# LDR.net
KiCad netlist of a schematic drawn in EAGLE
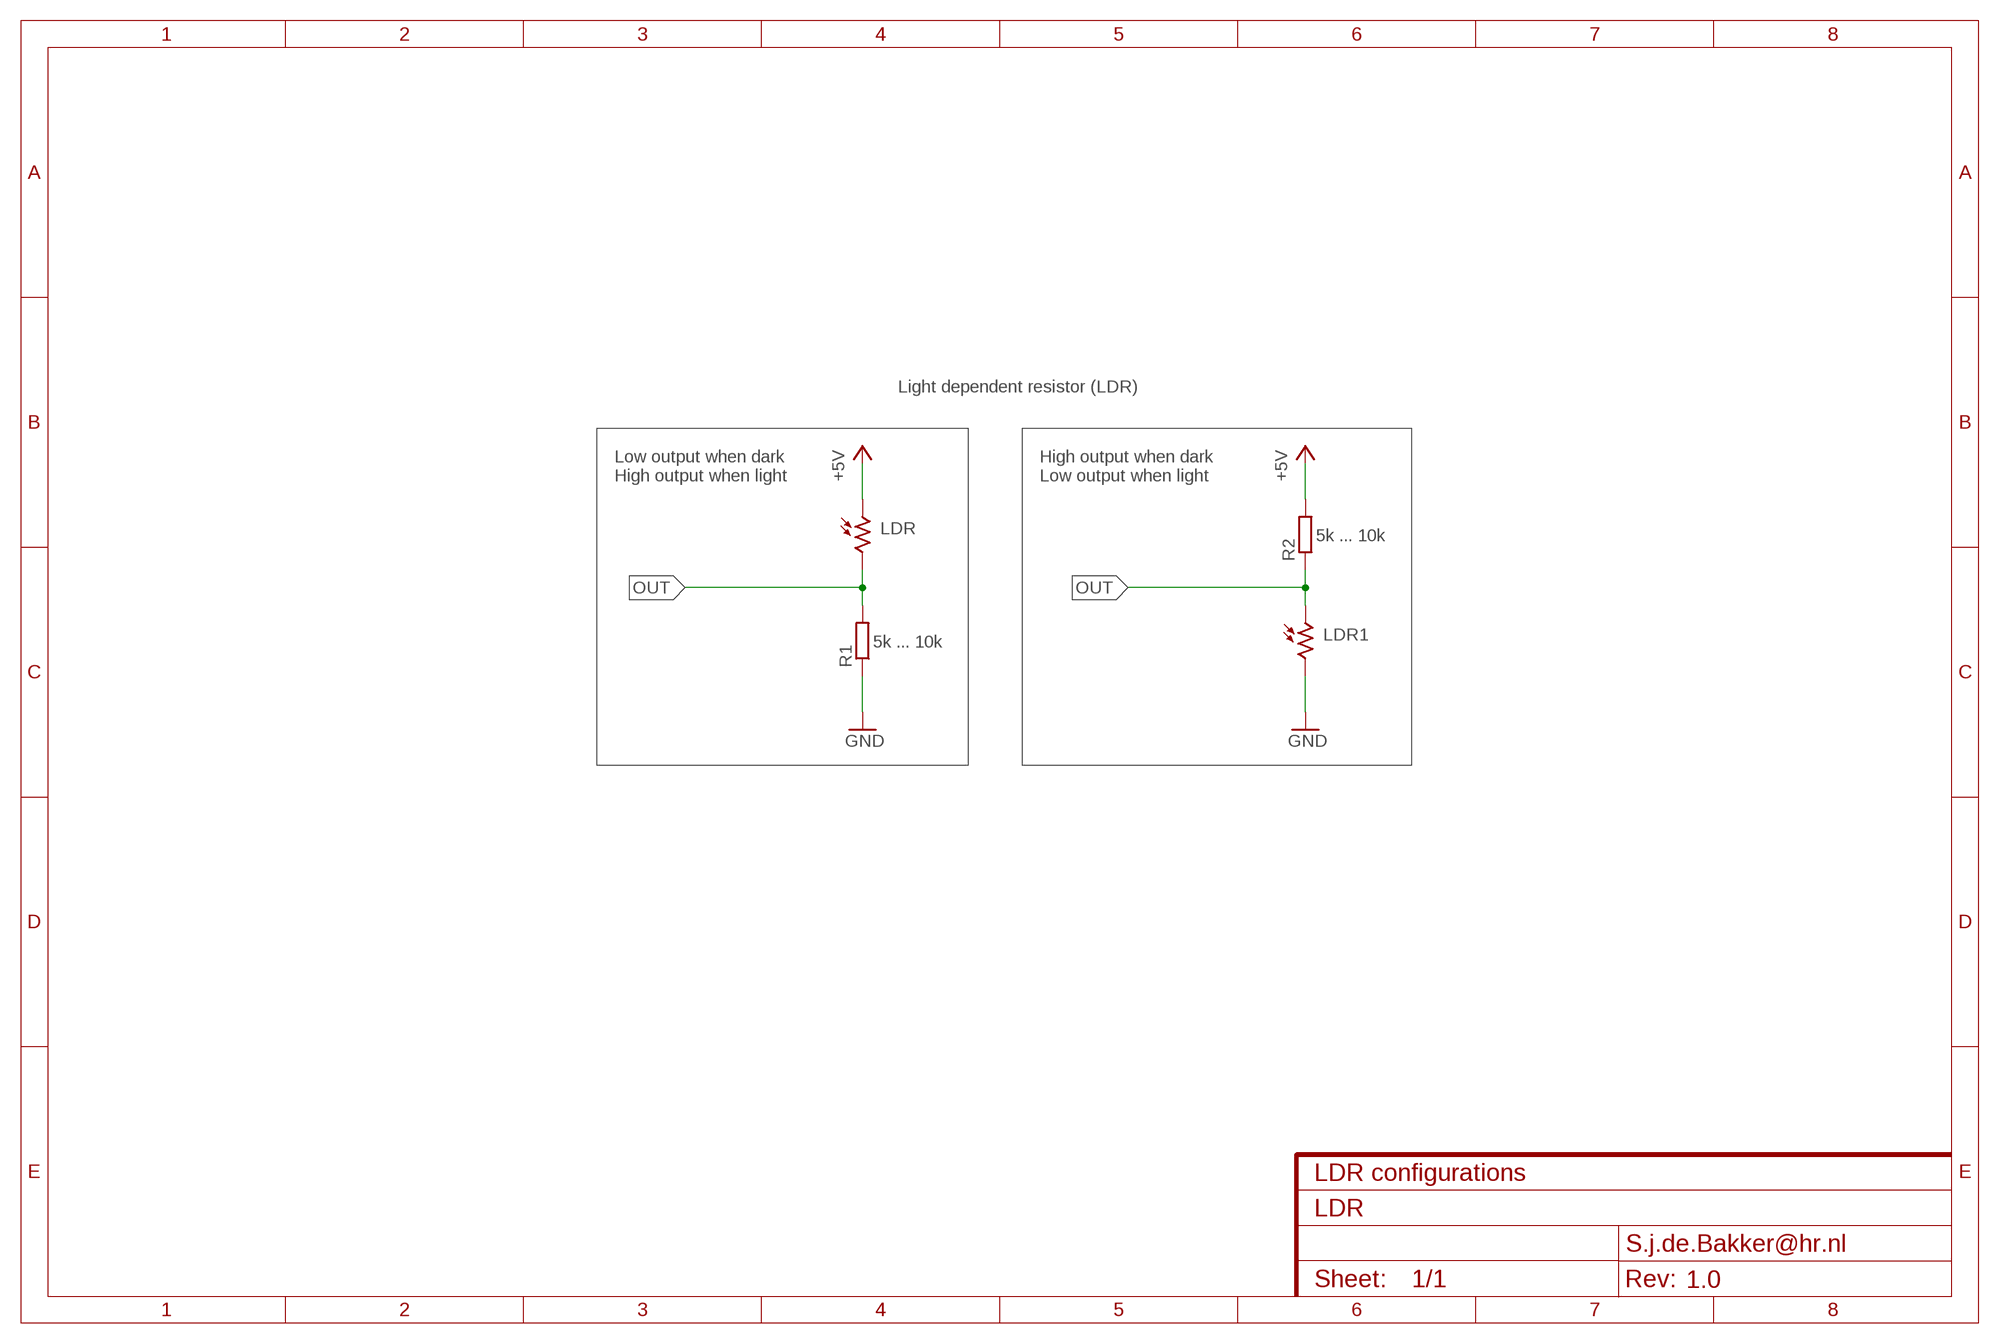
[diagram p0: schematic, sheet 1]

(export (version "E")
  (design (tool "Eeschema 10.0.6"))
  (components
    (comp (ref "LDR")
      (value "B1060_23")
      (footprint "eagle-import:TO-8_B10")
      (libsource (lib "eagle-import") (part "?1060B_23"))
    )
    (comp (ref "LDR1")
      (value "B1060_23")
      (footprint "eagle-import:TO-8_B10")
      (libsource (lib "eagle-import") (part "?1060B_23"))
    )
    (comp (ref "R1")
      (value "5k ... 10k")
      (footprint "eagle-import:VTA52")
      (libsource (lib "eagle-import") (part "R-EU_VTA52"))
    )
    (comp (ref "R2")
      (value "5k ... 10k")
      (footprint "eagle-import:VTA52")
      (libsource (lib "eagle-import") (part "R-EU_VTA52"))
    )
  )
  (nets
    (net (code "1") (name "+5V") (class "Default")
      (node (ref "LDR") (pin "1") (pinfunction "1_1") (pintype "passive"))
      (node (ref "R2") (pin "2") (pinfunction "2_2") (pintype "passive"))
    )
    (net (code "2") (name "GND") (class "Default")
      (node (ref "LDR1") (pin "2") (pinfunction "2_2") (pintype "passive"))
      (node (ref "R1") (pin "1") (pinfunction "1_1") (pintype "passive"))
    )
    (net (code "3") (name "OUT") (class "Default")
      (node (ref "LDR") (pin "2") (pinfunction "2_2") (pintype "passive"))
      (node (ref "LDR1") (pin "1") (pinfunction "1_1") (pintype "passive"))
      (node (ref "R1") (pin "2") (pinfunction "2_2") (pintype "passive"))
      (node (ref "R2") (pin "1") (pinfunction "1_1") (pintype "passive"))
    )
  )
)
